# Sheet2.net
KiCad netlist of a schematic drawn in Altium Designer
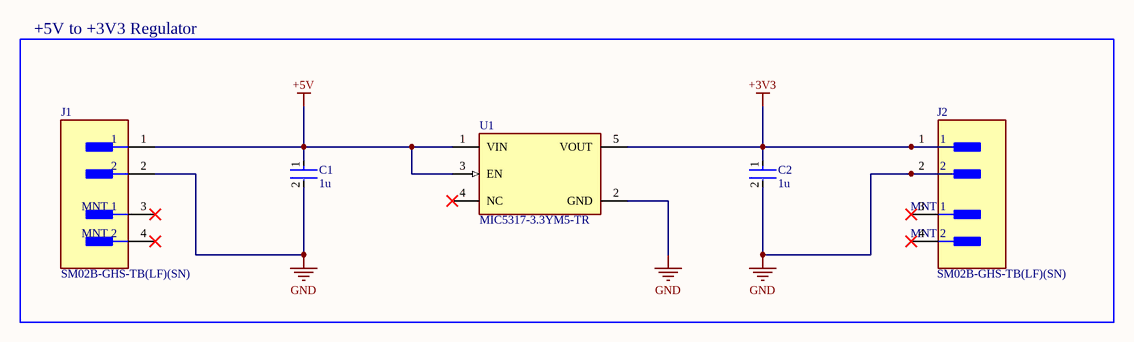
[diagram p0: Sheet2.SchDoc]

(export (version "E")
  (design (tool "Eeschema 10.0.6"))
  (components
    (comp (ref "C1")
      (value "1u")
      (footprint "FP-CC0805-0_85-MFG")
      (description "CAP CER 1UF 10V X7R 0805")
      (fields
        (field (name "MANUFACTURER") "Yageo")
        (field (name "OCTOPART") "https://octopart.com/cc0805kkx7r6bb105-yageo-42522859")
      )
      (libsource (lib "Altium Content Vault") (part "11868f565c42a9108669ba33697ecf6"))
    )
    (comp (ref "C2")
      (value "1u")
      (footprint "FP-CC0805-0_85-MFG")
      (description "CAP CER 1UF 10V X7R 0805")
      (fields
        (field (name "MANUFACTURER") "Yageo")
        (field (name "OCTOPART") "https://octopart.com/cc0805kkx7r6bb105-yageo-42522859")
      )
      (libsource (lib "Altium Content Vault") (part "11868f565c42a9108669ba33697ecf6"))
    )
    (comp (ref "J1")
      (value "SM02B-GHS-TB(LF)(SN)")
      (footprint "FP-SM02B-GHS-TB_LF_SN-MFG")
      (description "CONN HEADER SMD R/A 2POS 1.25MM")
      (libsource (lib "Altium Content Vault") (part "56ec3178a87b3978bdc1b3682cd516a"))
    )
    (comp (ref "J2")
      (value "SM02B-GHS-TB(LF)(SN)")
      (footprint "FP-SM02B-GHS-TB_LF_SN-MFG")
      (description "CONN HEADER SMD R/A 2POS 1.25MM")
      (libsource (lib "") (part "56ec3178a87b3978bdc1b3682cd516a_1"))
    )
    (comp (ref "U1")
      (value "MIC5317-3.3YM5-TR")
      (footprint "FP-SOT23-5LD-PL-1-MFG")
      (description "IC REG LINEAR 3.3V 150MA SOT23-5")
      (libsource (lib "Altium Content Vault") (part "0a093dae7315cdc977fd108dde87457"))
    )
  )
  (nets
    (net (code "1") (name "+3V3") (class "Default")
      (node (ref "C2") (pin "1") (pinfunction "1_1") (pintype "passive"))
      (node (ref "J2") (pin "1") (pinfunction "1_1") (pintype "passive"))
      (node (ref "U1") (pin "5") (pinfunction "VOUT_5") (pintype "power_in"))
    )
    (net (code "2") (name "+5V") (class "Default")
      (node (ref "C1") (pin "1") (pinfunction "1_1") (pintype "passive"))
      (node (ref "J1") (pin "1") (pinfunction "1_1") (pintype "passive"))
      (node (ref "U1") (pin "1") (pinfunction "VIN_1") (pintype "power_in"))
      (node (ref "U1") (pin "3") (pinfunction "EN_3") (pintype "input"))
    )
    (net (code "3") (name "GND") (class "Default")
      (node (ref "C1") (pin "2") (pinfunction "2_2") (pintype "passive"))
      (node (ref "C2") (pin "2") (pinfunction "2_2") (pintype "passive"))
      (node (ref "J1") (pin "2") (pinfunction "2_2") (pintype "passive"))
      (node (ref "J2") (pin "2") (pinfunction "2_2") (pintype "passive"))
      (node (ref "U1") (pin "2") (pinfunction "GND_2") (pintype "power_in"))
    )
    (net (code "4") (name "unconnected-(J1-MNT_1-Pad3)") (class "Default")
      (node (ref "J1") (pin "3") (pinfunction "MNT_1_3") (pintype "passive+no_connect"))
    )
    (net (code "5") (name "unconnected-(J1-MNT_2-Pad4)") (class "Default")
      (node (ref "J1") (pin "4") (pinfunction "MNT_2_4") (pintype "passive+no_connect"))
    )
    (net (code "6") (name "unconnected-(J2-MNT_1-Pad3)") (class "Default")
      (node (ref "J2") (pin "3") (pinfunction "MNT_1_3") (pintype "passive+no_connect"))
    )
    (net (code "7") (name "unconnected-(J2-MNT_2-Pad4)") (class "Default")
      (node (ref "J2") (pin "4") (pinfunction "MNT_2_4") (pintype "passive+no_connect"))
    )
    (net (code "8") (name "unconnected-(U1-NC-Pad4)") (class "Default")
      (node (ref "U1") (pin "4") (pinfunction "NC_4") (pintype "passive+no_connect"))
    )
  )
)
